# pulse_generator_pen.net
KiCad netlist of a schematic drawn in Altium Designer
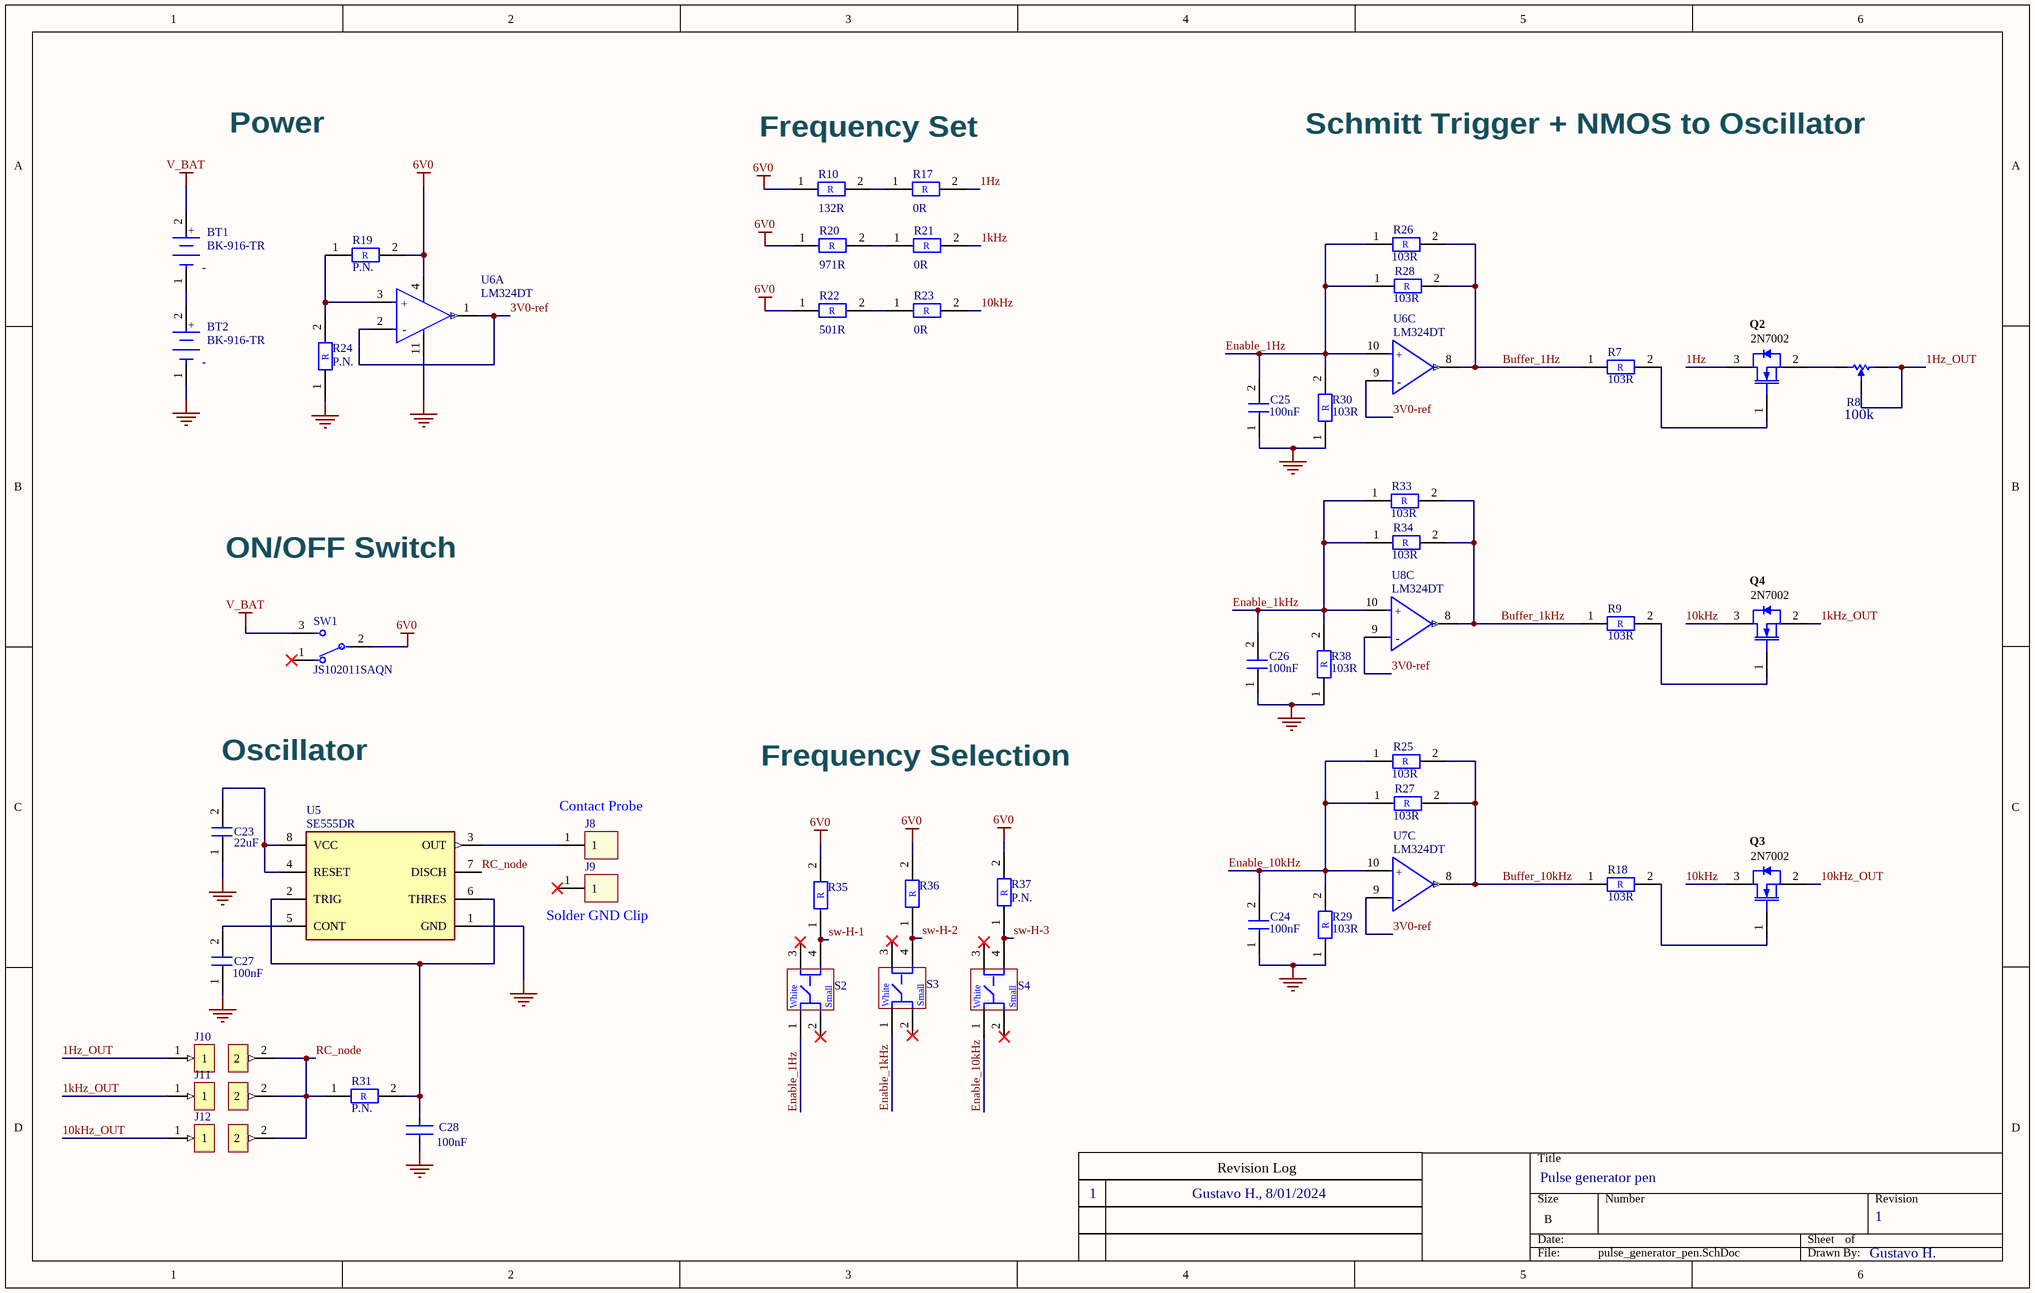
[diagram p0: pulse_generator_pen.SchDoc]

(export (version "E")
  (design (tool "Eeschema 10.0.6"))
  (components
    (comp (ref "BT1")
      (value "BK-916-TR")
      (footprint "FP-BK-916-TR-MFG")
      (description "BATTERY RETAINER COIN 12MM SMD")
      (libsource (lib "Altium Content Vault") (part "a5284bd3cf3b31494a5f032c79b9da8"))
    )
    (comp (ref "BT2")
      (value "BK-916-TR")
      (footprint "FP-BK-916-TR-MFG")
      (description "BATTERY RETAINER COIN 12MM SMD")
      (libsource (lib "Altium Content Vault") (part "a5284bd3cf3b31494a5f032c79b9da8"))
    )
    (comp (ref "C23")
      (value "P.N.")
      (footprint "0805_R")
      (description "Generic 0805 Capacitor")
      (fields (field (name "CAPACITANCE") "22uF"))
      (libsource (lib "CREEA_starter_library") (part "0805_C"))
    )
    (comp (ref "C24")
      (value "P.N.")
      (footprint "0805_R")
      (description "Generic 0805 Capacitor")
      (fields (field (name "CAPACITANCE") "100nF"))
      (libsource (lib "CREEA_starter_library") (part "0805_C"))
    )
    (comp (ref "C25")
      (value "P.N.")
      (footprint "0805_R")
      (description "Generic 0805 Capacitor")
      (fields (field (name "CAPACITANCE") "100nF"))
      (libsource (lib "CREEA_starter_library") (part "0805_C"))
    )
    (comp (ref "C26")
      (value "P.N.")
      (footprint "0805_R")
      (description "Generic 0805 Capacitor")
      (fields (field (name "CAPACITANCE") "100nF"))
      (libsource (lib "CREEA_starter_library") (part "0805_C"))
    )
    (comp (ref "C27")
      (value "P.N.")
      (footprint "0805_R")
      (description "Generic 0805 Capacitor")
      (fields (field (name "CAPACITANCE") "100nF"))
      (libsource (lib "CREEA_starter_library") (part "0805_C"))
    )
    (comp (ref "C28")
      (value "CL21B104KBCNNNC")
      (footprint "FP-CL21-IPC_A")
      (description "CL21 Series 0805 100nF 50V ±10% Tolerance X7R Multilayer Ceramic Chip Capacitor")
      (fields
        (field (name "TOLERANCE") "10%")
        (field (name "CAPACITANCE") "100nF")
        (field (name "VOLTAGE") "50V")
      )
      (libsource (lib "Altium Content Vault") (part "b4654b650e69147ec39a6b967a45e02"))
    )
    (comp (ref "J8")
      (value "HEADER_1POS_MALE")
      (footprint "HEADER_1POS_MALE_VERT_2.54MM")
      (libsource (lib "CREEA_starter_library") (part "HEADER_1POS_MALE"))
    )
    (comp (ref "J9")
      (value "HEADER_1POS_MALE")
      (footprint "HEADER_1POS_MALE_VERT_2.54MM")
      (libsource (lib "CREEA_starter_library") (part "HEADER_1POS_MALE"))
    )
    (comp (ref "J10")
      (value "JUMPER_RECT")
      (description "Small rectangular jumper")
      (libsource (lib "CREEA_starter_library") (part "JUMPER_RECT"))
    )
    (comp (ref "J11")
      (value "JUMPER_RECT")
      (description "Small rectangular jumper")
      (libsource (lib "CREEA_starter_library") (part "JUMPER_RECT"))
    )
    (comp (ref "J12")
      (value "JUMPER_RECT")
      (description "Small rectangular jumper")
      (libsource (lib "CREEA_starter_library") (part "JUMPER_RECT"))
    )
    (comp (ref "Q2")
      (value "2N7002")
      (footprint "INF-PG-SOT23_M")
      (fields (field (name "MANUFACTURER") "Infineon"))
      (libsource (lib "Altium Content Vault") (part "INF-NDMOS-GSD-3"))
    )
    (comp (ref "Q3")
      (value "2N7002")
      (footprint "INF-PG-SOT23_M")
      (fields (field (name "MANUFACTURER") "Infineon"))
      (libsource (lib "Altium Content Vault") (part "INF-NDMOS-GSD-3"))
    )
    (comp (ref "Q4")
      (value "2N7002")
      (footprint "INF-PG-SOT23_M")
      (fields (field (name "MANUFACTURER") "Infineon"))
      (libsource (lib "Altium Content Vault") (part "INF-NDMOS-GSD-3"))
    )
    (comp (ref "R7")
      (value "P.N.")
      (footprint "0805_R")
      (description "Generic 0805 Resistor")
      (fields (field (name "RESISTANCE") "103R"))
      (libsource (lib "CREEA_starter_library") (part "0805_R"))
    )
    (comp (ref "R8")
      (value "3296W-1-102LF")
      (footprint "BOUR-3296W-1-3")
      (description "Square Trimpot(R) Trimming Potentiometer, 1000 Ohm, -55 to 125 degC, 3-Pin THD, RoHS, Tube")
      (fields (field (name "TOLERANCE") "1%"))
      (libsource (lib "Altium Content Vault") (part "RES-ADJ-3"))
    )
    (comp (ref "R9")
      (value "P.N.")
      (footprint "0805_R")
      (description "Generic 0805 Resistor")
      (fields (field (name "RESISTANCE") "103R"))
      (libsource (lib "CREEA_starter_library") (part "0805_R"))
    )
    (comp (ref "R10")
      (value "P.N.")
      (footprint "0805_R")
      (description "Generic 0805 Resistor")
      (fields (field (name "RESISTANCE") "132R"))
      (libsource (lib "CREEA_starter_library") (part "0805_R"))
    )
    (comp (ref "R17")
      (value "P.N.")
      (footprint "0805_R")
      (description "Generic 0805 Resistor")
      (fields (field (name "RESISTANCE") "0R"))
      (libsource (lib "CREEA_starter_library") (part "0805_R"))
    )
    (comp (ref "R18")
      (value "P.N.")
      (footprint "0805_R")
      (description "Generic 0805 Resistor")
      (fields (field (name "RESISTANCE") "103R"))
      (libsource (lib "CREEA_starter_library") (part "0805_R"))
    )
    (comp (ref "R19")
      (value "P.N.")
      (footprint "0805_R")
      (description "Generic 0805 Resistor")
      (libsource (lib "CREEA_starter_library") (part "0805_R"))
    )
    (comp (ref "R20")
      (value "P.N.")
      (footprint "0805_R")
      (description "Generic 0805 Resistor")
      (fields (field (name "RESISTANCE") "971R"))
      (libsource (lib "CREEA_starter_library") (part "0805_R"))
    )
    (comp (ref "R21")
      (value "P.N.")
      (footprint "0805_R")
      (description "Generic 0805 Resistor")
      (fields (field (name "RESISTANCE") "0R"))
      (libsource (lib "CREEA_starter_library") (part "0805_R"))
    )
    (comp (ref "R22")
      (value "P.N.")
      (footprint "0805_R")
      (description "Generic 0805 Resistor")
      (fields (field (name "RESISTANCE") "501R"))
      (libsource (lib "CREEA_starter_library") (part "0805_R"))
    )
    (comp (ref "R23")
      (value "P.N.")
      (footprint "0805_R")
      (description "Generic 0805 Resistor")
      (fields (field (name "RESISTANCE") "0R"))
      (libsource (lib "CREEA_starter_library") (part "0805_R"))
    )
    (comp (ref "R24")
      (value "P.N.")
      (footprint "0805_R")
      (description "Generic 0805 Resistor")
      (libsource (lib "") (part "0805_R_1"))
    )
    (comp (ref "R25")
      (value "P.N.")
      (footprint "0805_R")
      (description "Generic 0805 Resistor")
      (fields (field (name "RESISTANCE") "103R"))
      (libsource (lib "CREEA_starter_library") (part "0805_R"))
    )
    (comp (ref "R26")
      (value "P.N.")
      (footprint "0805_R")
      (description "Generic 0805 Resistor")
      (fields (field (name "RESISTANCE") "103R"))
      (libsource (lib "CREEA_starter_library") (part "0805_R"))
    )
    (comp (ref "R27")
      (value "P.N.")
      (footprint "0805_R")
      (description "Generic 0805 Resistor")
      (fields (field (name "RESISTANCE") "103R"))
      (libsource (lib "CREEA_starter_library") (part "0805_R"))
    )
    (comp (ref "R28")
      (value "P.N.")
      (footprint "0805_R")
      (description "Generic 0805 Resistor")
      (fields (field (name "RESISTANCE") "103R"))
      (libsource (lib "CREEA_starter_library") (part "0805_R"))
    )
    (comp (ref "R29")
      (value "P.N.")
      (footprint "0805_R")
      (description "Generic 0805 Resistor")
      (fields (field (name "RESISTANCE") "103R"))
      (libsource (lib "") (part "0805_R_1"))
    )
    (comp (ref "R30")
      (value "P.N.")
      (footprint "0805_R")
      (description "Generic 0805 Resistor")
      (fields (field (name "RESISTANCE") "103R"))
      (libsource (lib "") (part "0805_R_1"))
    )
    (comp (ref "R31")
      (value "P.N.")
      (footprint "0805_R")
      (description "Generic 0805 Resistor")
      (libsource (lib "CREEA_starter_library") (part "0805_R"))
    )
    (comp (ref "R33")
      (value "P.N.")
      (footprint "0805_R")
      (description "Generic 0805 Resistor")
      (fields (field (name "RESISTANCE") "103R"))
      (libsource (lib "CREEA_starter_library") (part "0805_R"))
    )
    (comp (ref "R34")
      (value "P.N.")
      (footprint "0805_R")
      (description "Generic 0805 Resistor")
      (fields (field (name "RESISTANCE") "103R"))
      (libsource (lib "CREEA_starter_library") (part "0805_R"))
    )
    (comp (ref "R35")
      (value "P.N.")
      (footprint "0805_R")
      (description "Generic 0805 Resistor")
      (libsource (lib "") (part "0805_R_1"))
    )
    (comp (ref "R36")
      (value "P.N.")
      (footprint "0805_R")
      (description "Generic 0805 Resistor")
      (libsource (lib "") (part "0805_R_1"))
    )
    (comp (ref "R37")
      (value "P.N.")
      (footprint "0805_R")
      (description "Generic 0805 Resistor")
      (libsource (lib "") (part "0805_R_1"))
    )
    (comp (ref "R38")
      (value "P.N.")
      (footprint "0805_R")
      (description "Generic 0805 Resistor")
      (fields (field (name "RESISTANCE") "103R"))
      (libsource (lib "") (part "0805_R_1"))
    )
    (comp (ref "S2")
      (value "TACT_SWITCH_SMD_5x3MM")
      (footprint "TACT_SWITCH_SMD_5x3MM")
      (libsource (lib "CREEA_starter_library") (part "TACT_SWITCH_SMD_5x3MM"))
    )
    (comp (ref "S3")
      (value "TACT_SWITCH_SMD_5x3MM")
      (footprint "TACT_SWITCH_SMD_5x3MM")
      (libsource (lib "CREEA_starter_library") (part "TACT_SWITCH_SMD_5x3MM"))
    )
    (comp (ref "S4")
      (value "TACT_SWITCH_SMD_5x3MM")
      (footprint "TACT_SWITCH_SMD_5x3MM")
      (libsource (lib "CREEA_starter_library") (part "TACT_SWITCH_SMD_5x3MM"))
    )
    (comp (ref "SW1")
      (value "JS102011SAQN")
      (footprint "FP-JS102011SAQN-MFG")
      (description "SWITCH SLIDE SPDT 300MA 6V")
      (libsource (lib "Altium Content Vault") (part "39e195cbbadc85d1df0d7eb6847d379"))
    )
    (comp (ref "U5")
      (value "SE555DR")
      (footprint "FP-D0008A-MFG")
      (description "IC OSC SGL TIMER 100KHZ 8-SOIC")
      (libsource (lib "Altium Content Vault") (part "dd5b8434f2346953fd8290325fbf3de"))
    )
    (comp (ref "U6")
      (value "LM324DT")
      (footprint "FP-SO-14-MFG")
      (description "IC OPAMP GP 4 CIRCUIT 14SO")
      (fields
        (field (name "OCTOPART") "https://octopart.com/lm324dt-stmicroelectronics-39579146")
        (field (name "MANUFACTURER") "STMicroelectronics")
      )
      (libsource (lib "Altium Content Vault") (part "a065ef67e5aa9ef3942d43d6008d043"))
    )
    (comp (ref "U7")
      (value "LM324DT")
      (footprint "FP-SO-14-MFG")
      (description "IC OPAMP GP 4 CIRCUIT 14SO")
      (fields
        (field (name "OCTOPART") "https://octopart.com/lm324dt-stmicroelectronics-39579146")
        (field (name "MANUFACTURER") "STMicroelectronics")
      )
      (libsource (lib "Altium Content Vault") (part "a065ef67e5aa9ef3942d43d6008d043"))
    )
    (comp (ref "U8")
      (value "LM324DT")
      (footprint "FP-SO-14-MFG")
      (description "IC OPAMP GP 4 CIRCUIT 14SO")
      (fields
        (field (name "OCTOPART") "https://octopart.com/lm324dt-stmicroelectronics-39579146")
        (field (name "MANUFACTURER") "STMicroelectronics")
      )
      (libsource (lib "Altium Content Vault") (part "a065ef67e5aa9ef3942d43d6008d043"))
    )
  )
  (nets
    (net (code "1") (name "/1Hz") (class "Default")
      (node (ref "Q2") (pin "3") (pinfunction "DRAIN_3") (pintype "passive"))
      (node (ref "R17") (pin "2") (pinfunction "2_2") (pintype "passive"))
    )
    (net (code "2") (name "/1Hz_OUT") (class "Default")
      (node (ref "J10") (pin "1") (pinfunction "1_1") (pintype "input"))
      (node (ref "R8") (pin "2") (pinfunction "B_2") (pintype "passive"))
      (node (ref "R8") (pin "3") (pinfunction "TAP_3") (pintype "passive"))
    )
    (net (code "3") (name "/1kHz") (class "Default")
      (node (ref "R21") (pin "2") (pinfunction "2_2") (pintype "passive"))
    )
    (net (code "4") (name "/1kHz_OUT") (class "Default")
      (node (ref "J11") (pin "1") (pinfunction "1_1") (pintype "input"))
      (node (ref "Q4") (pin "2") (pinfunction "SOURCE_2") (pintype "passive"))
    )
    (net (code "5") (name "/3V0-ref") (class "Default")
      (node (ref "U6") (pin "1") (pinfunction "Output_1_1") (pintype "output"))
      (node (ref "U6") (pin "2") (pinfunction "Inverting_Input_1_2") (pintype "tri_state"))
      (node (ref "U6") (pin "9") (pinfunction "Inverting_Input_3_9") (pintype "tri_state"))
      (node (ref "U7") (pin "9") (pinfunction "Inverting_Input_3_9") (pintype "tri_state"))
      (node (ref "U8") (pin "9") (pinfunction "Inverting_Input_3_9") (pintype "tri_state"))
    )
    (net (code "6") (name "/10kHz") (class "Default")
      (node (ref "Q3") (pin "3") (pinfunction "DRAIN_3") (pintype "passive"))
      (node (ref "Q4") (pin "3") (pinfunction "DRAIN_3") (pintype "passive"))
      (node (ref "R23") (pin "2") (pinfunction "2_2") (pintype "passive"))
    )
    (net (code "7") (name "/10kHz_OUT") (class "Default")
      (node (ref "J12") (pin "1") (pinfunction "1_1") (pintype "input"))
      (node (ref "Q3") (pin "2") (pinfunction "SOURCE_2") (pintype "passive"))
    )
    (net (code "8") (name "/Buffer_1Hz") (class "Default")
      (node (ref "R26") (pin "2") (pinfunction "2_2") (pintype "passive"))
      (node (ref "R28") (pin "2") (pinfunction "2_2") (pintype "passive"))
      (node (ref "R7") (pin "1") (pinfunction "1_1") (pintype "passive"))
      (node (ref "U6") (pin "8") (pinfunction "Output_3_8") (pintype "output"))
    )
    (net (code "9") (name "/Buffer_1kHz") (class "Default")
      (node (ref "R33") (pin "2") (pinfunction "2_2") (pintype "passive"))
      (node (ref "R34") (pin "2") (pinfunction "2_2") (pintype "passive"))
      (node (ref "R9") (pin "1") (pinfunction "1_1") (pintype "passive"))
      (node (ref "U8") (pin "8") (pinfunction "Output_3_8") (pintype "output"))
    )
    (net (code "10") (name "/Buffer_10kHz") (class "Default")
      (node (ref "R18") (pin "1") (pinfunction "1_1") (pintype "passive"))
      (node (ref "R25") (pin "2") (pinfunction "2_2") (pintype "passive"))
      (node (ref "R27") (pin "2") (pinfunction "2_2") (pintype "passive"))
      (node (ref "U7") (pin "8") (pinfunction "Output_3_8") (pintype "output"))
    )
    (net (code "11") (name "/Enable_1Hz") (class "Default")
      (node (ref "C25") (pin "2") (pinfunction "2_2") (pintype "passive"))
      (node (ref "R26") (pin "1") (pinfunction "1_1") (pintype "passive"))
      (node (ref "R28") (pin "1") (pinfunction "1_1") (pintype "passive"))
      (node (ref "R30") (pin "2") (pinfunction "2_2") (pintype "passive"))
      (node (ref "S2") (pin "1") (pinfunction "1_1") (pintype "passive"))
      (node (ref "U6") (pin "10") (pinfunction "Non-Inverting_Input_3_10") (pintype "tri_state"))
    )
    (net (code "12") (name "/Enable_1kHz") (class "Default")
      (node (ref "C26") (pin "2") (pinfunction "2_2") (pintype "passive"))
      (node (ref "R33") (pin "1") (pinfunction "1_1") (pintype "passive"))
      (node (ref "R34") (pin "1") (pinfunction "1_1") (pintype "passive"))
      (node (ref "R38") (pin "2") (pinfunction "2_2") (pintype "passive"))
      (node (ref "S3") (pin "1") (pinfunction "1_1") (pintype "passive"))
      (node (ref "U8") (pin "10") (pinfunction "Non-Inverting_Input_3_10") (pintype "tri_state"))
    )
    (net (code "13") (name "/Enable_10kHz") (class "Default")
      (node (ref "C24") (pin "2") (pinfunction "2_2") (pintype "passive"))
      (node (ref "R25") (pin "1") (pinfunction "1_1") (pintype "passive"))
      (node (ref "R27") (pin "1") (pinfunction "1_1") (pintype "passive"))
      (node (ref "R29") (pin "2") (pinfunction "2_2") (pintype "passive"))
      (node (ref "S4") (pin "1") (pinfunction "1_1") (pintype "passive"))
      (node (ref "U7") (pin "10") (pinfunction "Non-Inverting_Input_3_10") (pintype "tri_state"))
    )
    (net (code "14") (name "/RC_node") (class "Default")
      (node (ref "J10") (pin "2") (pinfunction "2_2") (pintype "output"))
      (node (ref "J11") (pin "2") (pinfunction "2_2") (pintype "output"))
      (node (ref "J12") (pin "2") (pinfunction "2_2") (pintype "output"))
      (node (ref "R31") (pin "1") (pinfunction "1_1") (pintype "passive"))
      (node (ref "U5") (pin "7") (pinfunction "DISCH_7") (pintype "passive"))
    )
    (net (code "15") (name "/sw-H-1") (class "Default")
      (node (ref "R35") (pin "1") (pinfunction "1_1") (pintype "passive"))
      (node (ref "S2") (pin "4") (pinfunction "4_4") (pintype "passive"))
    )
    (net (code "16") (name "/sw-H-2") (class "Default")
      (node (ref "R36") (pin "1") (pinfunction "1_1") (pintype "passive"))
      (node (ref "S3") (pin "4") (pinfunction "4_4") (pintype "passive"))
    )
    (net (code "17") (name "/sw-H-3") (class "Default")
      (node (ref "R37") (pin "1") (pinfunction "1_1") (pintype "passive"))
      (node (ref "S4") (pin "4") (pinfunction "4_4") (pintype "passive"))
    )
    (net (code "18") (name "6V0") (class "Default")
      (node (ref "R10") (pin "1") (pinfunction "1_1") (pintype "passive"))
      (node (ref "R19") (pin "2") (pinfunction "2_2") (pintype "passive"))
      (node (ref "R20") (pin "1") (pinfunction "1_1") (pintype "passive"))
      (node (ref "R22") (pin "1") (pinfunction "1_1") (pintype "passive"))
      (node (ref "R35") (pin "2") (pinfunction "2_2") (pintype "passive"))
      (node (ref "R36") (pin "2") (pinfunction "2_2") (pintype "passive"))
      (node (ref "R37") (pin "2") (pinfunction "2_2") (pintype "passive"))
      (node (ref "SW1") (pin "2") (pinfunction "C_2") (pintype "passive"))
      (node (ref "U6") (pin "4") (pinfunction "VCC+_4") (pintype "power_in"))
    )
    (net (code "19") (name "GND") (class "Default")
      (node (ref "BT2") (pin "1") (pinfunction "C_1") (pintype "passive"))
      (node (ref "C23") (pin "1") (pinfunction "1_1") (pintype "passive"))
      (node (ref "C24") (pin "1") (pinfunction "1_1") (pintype "passive"))
      (node (ref "C25") (pin "1") (pinfunction "1_1") (pintype "passive"))
      (node (ref "C26") (pin "1") (pinfunction "1_1") (pintype "passive"))
      (node (ref "C27") (pin "1") (pinfunction "1_1") (pintype "passive"))
      (node (ref "C28") (pin "1") (pinfunction "1_1") (pintype "passive"))
      (node (ref "R24") (pin "1") (pinfunction "1_1") (pintype "passive"))
      (node (ref "R29") (pin "1") (pinfunction "1_1") (pintype "passive"))
      (node (ref "R30") (pin "1") (pinfunction "1_1") (pintype "passive"))
      (node (ref "R38") (pin "1") (pinfunction "1_1") (pintype "passive"))
      (node (ref "U5") (pin "1") (pinfunction "GND_1") (pintype "power_in"))
      (node (ref "U6") (pin "11") (pinfunction "VCC-_11") (pintype "power_in"))
    )
    (net (code "20") (name "Net-(BT1-C)") (class "Default")
      (node (ref "BT1") (pin "1") (pinfunction "C_1") (pintype "passive"))
      (node (ref "BT2") (pin "2") (pinfunction "A_2") (pintype "passive"))
    )
    (net (code "21") (name "Net-(Q2-GATE)") (class "Default")
      (node (ref "Q2") (pin "1") (pinfunction "GATE_1") (pintype "passive"))
      (node (ref "R7") (pin "2") (pinfunction "2_2") (pintype "passive"))
    )
    (net (code "22") (name "Net-(Q2-SOURCE)") (class "Default")
      (node (ref "Q2") (pin "2") (pinfunction "SOURCE_2") (pintype "passive"))
      (node (ref "R8") (pin "1") (pinfunction "A_1") (pintype "passive"))
    )
    (net (code "23") (name "Net-(Q3-GATE)") (class "Default")
      (node (ref "Q3") (pin "1") (pinfunction "GATE_1") (pintype "passive"))
      (node (ref "R18") (pin "2") (pinfunction "2_2") (pintype "passive"))
    )
    (net (code "24") (name "Net-(Q4-GATE)") (class "Default")
      (node (ref "Q4") (pin "1") (pinfunction "GATE_1") (pintype "passive"))
      (node (ref "R9") (pin "2") (pinfunction "2_2") (pintype "passive"))
    )
    (net (code "25") (name "Net-(R10-Pad2)") (class "Default")
      (node (ref "R10") (pin "2") (pinfunction "2_2") (pintype "passive"))
      (node (ref "R17") (pin "1") (pinfunction "1_1") (pintype "passive"))
    )
    (net (code "26") (name "Net-(R20-Pad2)") (class "Default")
      (node (ref "R20") (pin "2") (pinfunction "2_2") (pintype "passive"))
      (node (ref "R21") (pin "1") (pinfunction "1_1") (pintype "passive"))
    )
    (net (code "27") (name "Net-(R22-Pad2)") (class "Default")
      (node (ref "R22") (pin "2") (pinfunction "2_2") (pintype "passive"))
      (node (ref "R23") (pin "1") (pinfunction "1_1") (pintype "passive"))
    )
    (net (code "28") (name "Net-(U5-CONT)") (class "Default")
      (node (ref "C27") (pin "2") (pinfunction "2_2") (pintype "passive"))
      (node (ref "U5") (pin "5") (pinfunction "CONT_5") (pintype "passive"))
    )
    (net (code "29") (name "Net-(U5-OUT)") (class "Default")
      (node (ref "J8") (pin "1") (pinfunction "1_1") (pintype "passive"))
      (node (ref "U5") (pin "3") (pinfunction "OUT_3") (pintype "output"))
    )
    (net (code "30") (name "Net-(U5-RESET)") (class "Default")
      (node (ref "C23") (pin "2") (pinfunction "2_2") (pintype "passive"))
      (node (ref "U5") (pin "4") (pinfunction "RESET_4") (pintype "passive"))
      (node (ref "U5") (pin "8") (pinfunction "VCC_8") (pintype "power_in"))
    )
    (net (code "31") (name "Net-(U5-THRES)") (class "Default")
      (node (ref "C28") (pin "2") (pinfunction "2_2") (pintype "passive"))
      (node (ref "R31") (pin "2") (pinfunction "2_2") (pintype "passive"))
      (node (ref "U5") (pin "2") (pinfunction "TRIG_2") (pintype "passive"))
      (node (ref "U5") (pin "6") (pinfunction "THRES_6") (pintype "passive"))
    )
    (net (code "32") (name "Net-(U6A-Non-Inverting_Input_1)") (class "Default")
      (node (ref "R19") (pin "1") (pinfunction "1_1") (pintype "passive"))
      (node (ref "R24") (pin "2") (pinfunction "2_2") (pintype "passive"))
      (node (ref "U6") (pin "3") (pinfunction "Non-Inverting_Input_1_3") (pintype "tri_state"))
    )
    (net (code "33") (name "V_BAT") (class "Default")
      (node (ref "BT1") (pin "2") (pinfunction "A_2") (pintype "passive"))
      (node (ref "SW1") (pin "3") (pinfunction "3_3") (pintype "passive"))
    )
    (net (code "34") (name "unconnected-(J9-Pad1)") (class "Default")
      (node (ref "J9") (pin "1") (pinfunction "1_1") (pintype "passive+no_connect"))
    )
    (net (code "35") (name "unconnected-(S2-Pad2)") (class "Default")
      (node (ref "S2") (pin "2") (pinfunction "2_2") (pintype "passive+no_connect"))
    )
    (net (code "36") (name "unconnected-(S2-Pad3)") (class "Default")
      (node (ref "S2") (pin "3") (pinfunction "3_3") (pintype "passive+no_connect"))
    )
    (net (code "37") (name "unconnected-(S3-Pad2)") (class "Default")
      (node (ref "S3") (pin "2") (pinfunction "2_2") (pintype "passive+no_connect"))
    )
    (net (code "38") (name "unconnected-(S3-Pad3)") (class "Default")
      (node (ref "S3") (pin "3") (pinfunction "3_3") (pintype "passive+no_connect"))
    )
    (net (code "39") (name "unconnected-(S4-Pad2)") (class "Default")
      (node (ref "S4") (pin "2") (pinfunction "2_2") (pintype "passive+no_connect"))
    )
    (net (code "40") (name "unconnected-(S4-Pad3)") (class "Default")
      (node (ref "S4") (pin "3") (pinfunction "3_3") (pintype "passive+no_connect"))
    )
    (net (code "41") (name "unconnected-(SW1-Pad1)") (class "Default")
      (node (ref "SW1") (pin "1") (pinfunction "1_1") (pintype "passive+no_connect"))
    )
  )
)
